# schematicEagle.net
KiCad netlist of a schematic drawn in EAGLE
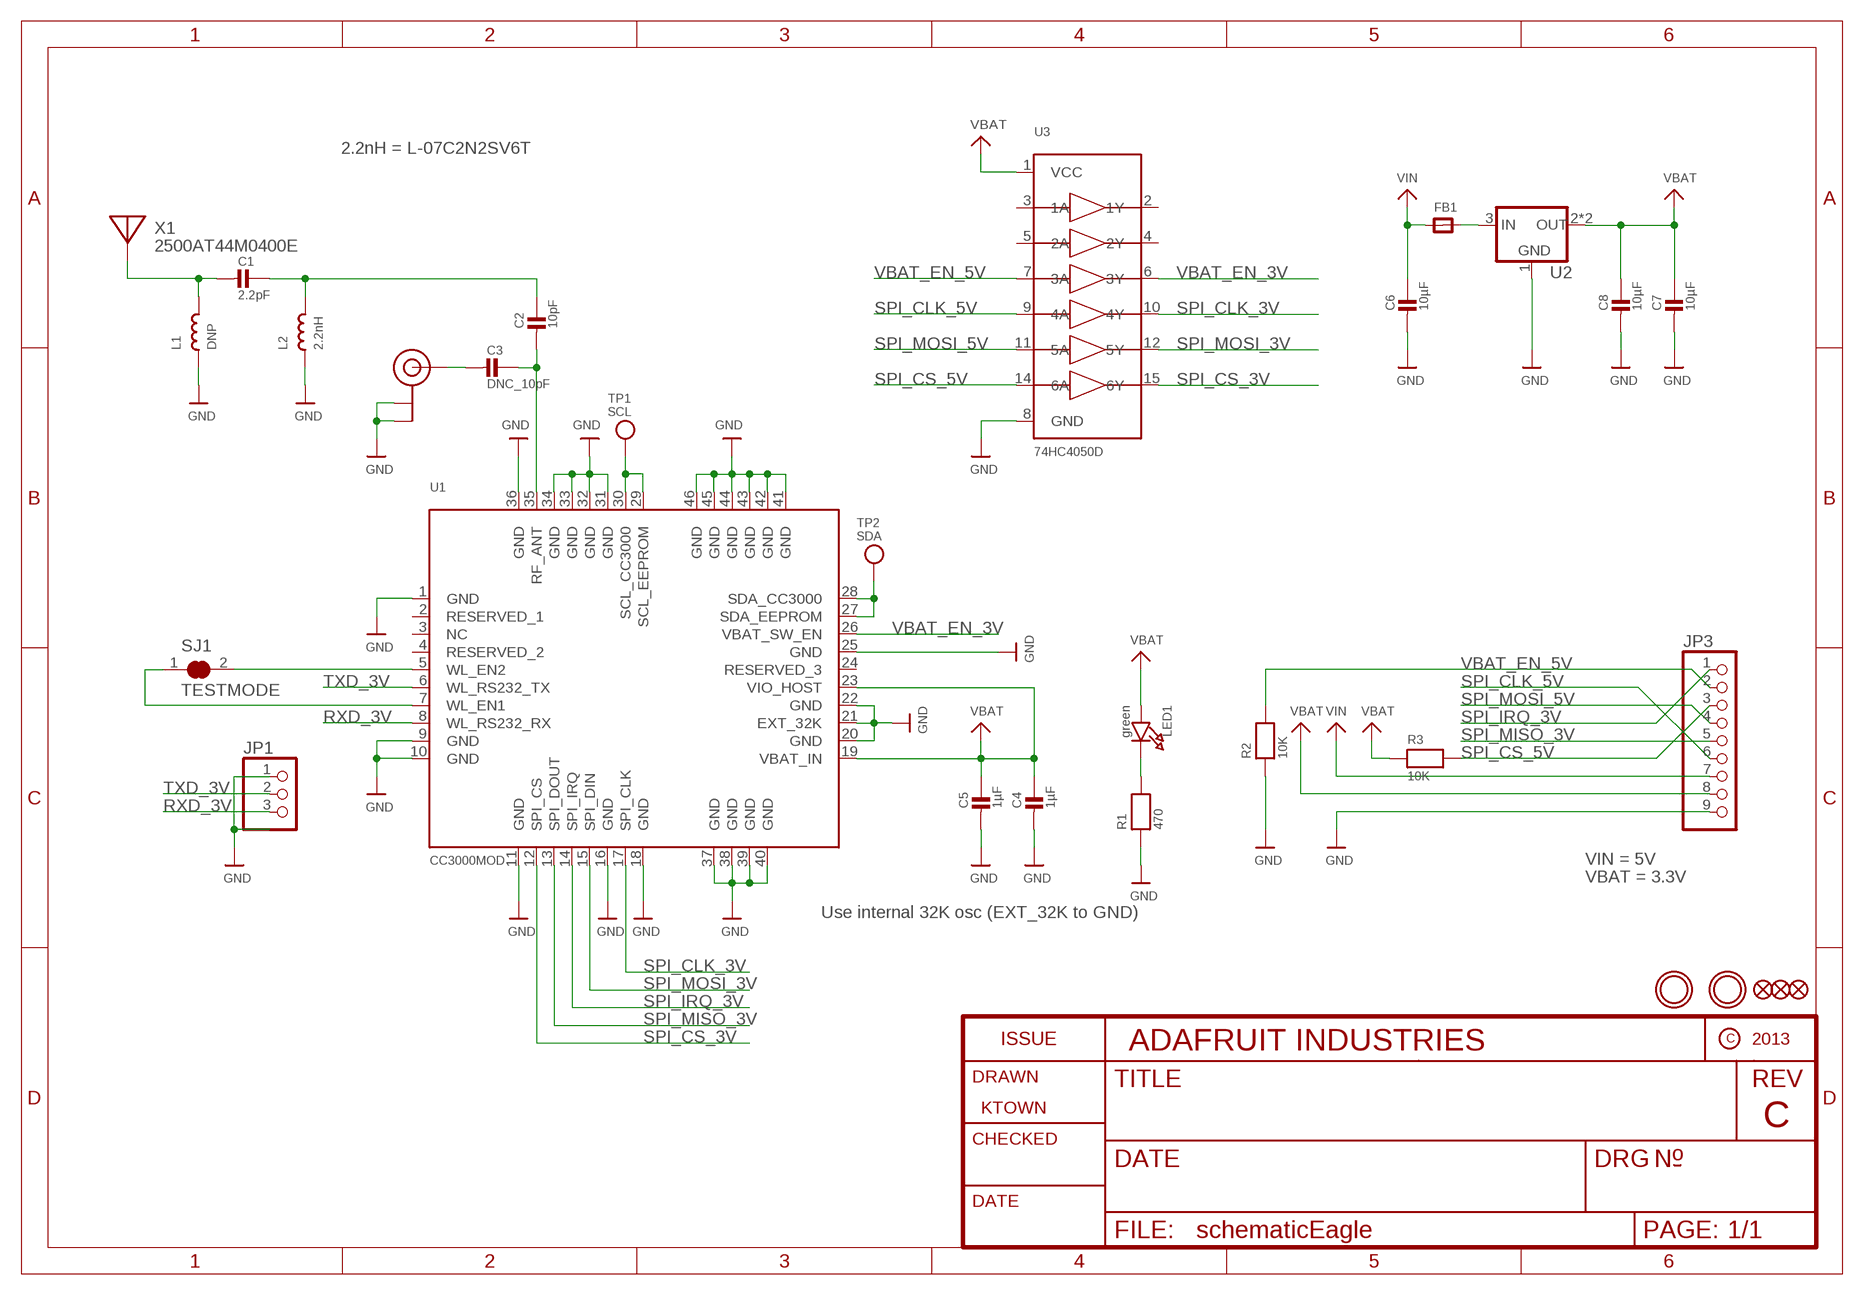
[diagram p0: schematic, sheet 1]

(export (version "E")
  (design (tool "Eeschema 10.0.6"))
  (components
    (comp (ref "C1")
      (value "2.2pF")
      (footprint "eagle-import:_0402")
      (libsource (lib "eagle-import") (part "CAP_CERAMIC_0402"))
    )
    (comp (ref "C2")
      (value "10pF")
      (footprint "eagle-import:_0402")
      (libsource (lib "eagle-import") (part "CAP_CERAMIC_0402"))
    )
    (comp (ref "C3")
      (value "DNC_10pF")
      (footprint "eagle-import:_0402")
      (libsource (lib "eagle-import") (part "CAP_CERAMIC_0402"))
    )
    (comp (ref "C4")
      (value "1µF")
      (footprint "eagle-import:_0805MP")
      (libsource (lib "eagle-import") (part "CAP_CERAMIC_0805MP"))
    )
    (comp (ref "C5")
      (value "1µF")
      (footprint "eagle-import:_0805MP")
      (libsource (lib "eagle-import") (part "CAP_CERAMIC_0805MP"))
    )
    (comp (ref "C6")
      (value "10µF")
      (footprint "eagle-import:_0805MP")
      (libsource (lib "eagle-import") (part "CAP_CERAMIC_0805MP"))
    )
    (comp (ref "C7")
      (value "10µF")
      (footprint "eagle-import:_0805MP")
      (libsource (lib "eagle-import") (part "CAP_CERAMIC_0805MP"))
    )
    (comp (ref "C8")
      (value "10µF")
      (footprint "eagle-import:_0805MP")
      (libsource (lib "eagle-import") (part "CAP_CERAMIC_0805MP"))
    )
    (comp (ref "FB1")
      (value "FERRITE_0805MP")
      (footprint "eagle-import:_0805MP")
      (libsource (lib "eagle-import") (part "FERRITE_0805MP"))
    )
    (comp (ref "FID1")
      (value "FIDUCIAL\"\"")
      (footprint "eagle-import:FIDUCIAL_1MM")
      (libsource (lib "eagle-import") (part "FIDUCIAL{dblquote}{dblquote}"))
    )
    (comp (ref "FID2")
      (value "FIDUCIAL\"\"")
      (footprint "eagle-import:FIDUCIAL_1MM")
      (libsource (lib "eagle-import") (part "FIDUCIAL{dblquote}{dblquote}"))
    )
    (comp (ref "FID3")
      (value "FIDUCIAL\"\"")
      (footprint "eagle-import:FIDUCIAL_1MM")
      (fields (field (name "BOM") "EXCLUDE"))
      (libsource (lib "eagle-import") (part "FIDUCIAL{dblquote}{dblquote}"))
    )
    (comp (ref "JP1")
      (value "HEADER-1X3ROUND")
      (footprint "eagle-import:1X03_ROUND")
      (libsource (lib "eagle-import") (part "HEADER-1X3ROUND"))
    )
    (comp (ref "JP3")
      (value "HEADER-1X970MIL")
      (footprint "eagle-import:1X09_ROUND_70")
      (libsource (lib "eagle-import") (part "HEADER-1X970MIL"))
    )
    (comp (ref "L1")
      (value "DNP")
      (footprint "eagle-import:_0402")
      (libsource (lib "eagle-import") (part "INDUCTOR_0402"))
    )
    (comp (ref "L2")
      (value "2.2nH")
      (footprint "eagle-import:_0402")
      (libsource (lib "eagle-import") (part "INDUCTOR_0402"))
    )
    (comp (ref "LED1")
      (value "green")
      (footprint "eagle-import:CHIPLED_0805_NOOUTLINE")
      (libsource (lib "eagle-import") (part "LED0805_NOOUTLINE"))
    )
    (comp (ref "R1")
      (value "470")
      (footprint "eagle-import:0805-NO")
      (libsource (lib "eagle-import") (part "RESISTOR0805_NOOUTLINE"))
    )
    (comp (ref "R2")
      (value "10K")
      (footprint "eagle-import:_0805MP")
      (libsource (lib "eagle-import") (part "RESISTOR_0805MP"))
    )
    (comp (ref "R3")
      (value "10K")
      (footprint "eagle-import:_0805MP")
      (libsource (lib "eagle-import") (part "RESISTOR_0805MP"))
    )
    (comp (ref "SJ1")
      (value "TESTMODE")
      (footprint "eagle-import:SOLDERJUMPER_CLOSEDWIRE")
      (libsource (lib "eagle-import") (part "SOLDERJUMPER_CLOSED"))
    )
    (comp (ref "TP1")
      (value "SCL")
      (footprint "eagle-import:TESTPOINT_PAD_1MM")
      (libsource (lib "eagle-import") (part "TESTPOINTPAD1MM"))
    )
    (comp (ref "TP2")
      (value "SDA")
      (footprint "eagle-import:TESTPOINT_PAD_1MM")
      (libsource (lib "eagle-import") (part "TESTPOINTPAD1MM"))
    )
    (comp (ref "U$24")
      (value "MOUNTINGHOLE2.5")
      (footprint "eagle-import:MOUNTINGHOLE_2.5_PLATED")
      (libsource (lib "eagle-import") (part "MOUNTINGHOLE2.5"))
    )
    (comp (ref "U$34")
      (value "MOUNTINGHOLE2.5")
      (footprint "eagle-import:MOUNTINGHOLE_2.5_PLATED")
      (libsource (lib "eagle-import") (part "MOUNTINGHOLE2.5"))
    )
    (comp (ref "U$35")
      (value "U.FL")
      (footprint "eagle-import:U.FL")
      (libsource (lib "eagle-import") (part "U.FL"))
    )
    (comp (ref "U1")
      (value "CC3000MOD")
      (footprint "eagle-import:CC3000MOD")
      (libsource (lib "eagle-import") (part "CC3000MOD"))
    )
    (comp (ref "U2")
      (value "VREG_SOT223")
      (footprint "eagle-import:SOT223-R")
      (libsource (lib "eagle-import") (part "VREG_SOT223"))
    )
    (comp (ref "U3")
      (value "74HC4050D")
      (footprint "eagle-import:SOIC16")
      (libsource (lib "eagle-import") (part "74HC4050D"))
    )
    (comp (ref "X1")
      (value "2500AT44M0400E")
      (footprint "eagle-import:ANT_2500AT44M0400")
      (libsource (lib "eagle-import") (part "ANTENNA_JOHANSON_2500AT44M0400"))
    )
  )
  (nets
    (net (code "1") (name "/RXD_3V") (class "Default")
      (node (ref "JP1") (pin "3") (pinfunction "3_3") (pintype "passive"))
      (node (ref "U1") (pin "8") (pinfunction "WL_RS232_RX_8") (pintype "input"))
    )
    (net (code "2") (name "/SPI_CLK_3V") (class "Default")
      (node (ref "U1") (pin "17") (pinfunction "SPI_CLK_17") (pintype "input"))
      (node (ref "U3") (pin "10") (pinfunction "4Y_10") (pintype "bidirectional"))
    )
    (net (code "3") (name "/SPI_CLK_5V") (class "Default")
      (node (ref "JP3") (pin "6") (pinfunction "6_6") (pintype "passive"))
      (node (ref "U3") (pin "9") (pinfunction "4A_9") (pintype "bidirectional"))
    )
    (net (code "4") (name "/SPI_CS_3V") (class "Default")
      (node (ref "U1") (pin "12") (pinfunction "SPI_CS_12") (pintype "input"))
      (node (ref "U3") (pin "15") (pinfunction "6Y_15") (pintype "bidirectional"))
    )
    (net (code "5") (name "/SPI_CS_5V") (class "Default")
      (node (ref "JP3") (pin "3") (pinfunction "3_3") (pintype "passive"))
      (node (ref "R3") (pin "2") (pinfunction "2_2") (pintype "passive"))
      (node (ref "U3") (pin "14") (pinfunction "6A_14") (pintype "bidirectional"))
    )
    (net (code "6") (name "/SPI_IRQ_3V") (class "Default")
      (node (ref "JP3") (pin "1") (pinfunction "1_1") (pintype "passive"))
      (node (ref "U1") (pin "14") (pinfunction "SPI_IRQ_14") (pintype "output"))
    )
    (net (code "7") (name "/SPI_MISO_3V") (class "Default")
      (node (ref "JP3") (pin "5") (pinfunction "5_5") (pintype "passive"))
      (node (ref "U1") (pin "13") (pinfunction "SPI_DOUT_13") (pintype "output"))
    )
    (net (code "8") (name "/SPI_MOSI_3V") (class "Default")
      (node (ref "U1") (pin "15") (pinfunction "SPI_DIN_15") (pintype "input"))
      (node (ref "U3") (pin "12") (pinfunction "5Y_12") (pintype "bidirectional"))
    )
    (net (code "9") (name "/SPI_MOSI_5V") (class "Default")
      (node (ref "JP3") (pin "4") (pinfunction "4_4") (pintype "passive"))
      (node (ref "U3") (pin "11") (pinfunction "5A_11") (pintype "bidirectional"))
    )
    (net (code "10") (name "/TXD_3V") (class "Default")
      (node (ref "JP1") (pin "2") (pinfunction "2_2") (pintype "passive"))
      (node (ref "U1") (pin "6") (pinfunction "WL_RS232_TX_6") (pintype "output"))
    )
    (net (code "11") (name "/VBAT_EN_3V") (class "Default")
      (node (ref "U1") (pin "26") (pinfunction "VBAT_SW_EN_26") (pintype "input"))
      (node (ref "U3") (pin "6") (pinfunction "3Y_6") (pintype "bidirectional"))
    )
    (net (code "12") (name "/VBAT_EN_5V") (class "Default")
      (node (ref "JP3") (pin "2") (pinfunction "2_2") (pintype "passive"))
      (node (ref "R2") (pin "2") (pinfunction "2_2") (pintype "passive"))
      (node (ref "U3") (pin "7") (pinfunction "3A_7") (pintype "bidirectional"))
    )
    (net (code "13") (name "GND") (class "Default")
      (node (ref "C4") (pin "2") (pinfunction "2_2") (pintype "passive"))
      (node (ref "C5") (pin "2") (pinfunction "2_2") (pintype "passive"))
      (node (ref "C6") (pin "2") (pinfunction "2_2") (pintype "passive"))
      (node (ref "C7") (pin "2") (pinfunction "2_2") (pintype "passive"))
      (node (ref "C8") (pin "2") (pinfunction "2_2") (pintype "passive"))
      (node (ref "JP1") (pin "1") (pinfunction "1_1") (pintype "passive"))
      (node (ref "JP3") (pin "9") (pinfunction "9_9") (pintype "passive"))
      (node (ref "L1") (pin "1") (pinfunction "1_1") (pintype "passive"))
      (node (ref "L2") (pin "1") (pinfunction "1_1") (pintype "passive"))
      (node (ref "R1") (pin "1") (pinfunction "1_1") (pintype "passive"))
      (node (ref "R2") (pin "1") (pinfunction "1_1") (pintype "passive"))
      (node (ref "U$35") (pin "P$1") (pinfunction "GND_P$1") (pintype "bidirectional"))
      (node (ref "U$35") (pin "P$2") (pinfunction "GND_P$2") (pintype "bidirectional"))
      (node (ref "U1") (pin "1") (pinfunction "GND_1") (pintype "power_in"))
      (node (ref "U1") (pin "10") (pinfunction "GND_10") (pintype "power_in"))
      (node (ref "U1") (pin "11") (pinfunction "GND_11") (pintype "power_in"))
      (node (ref "U1") (pin "16") (pinfunction "GND_16") (pintype "power_in"))
      (node (ref "U1") (pin "18") (pinfunction "GND_18") (pintype "power_in"))
      (node (ref "U1") (pin "20") (pinfunction "GND_20") (pintype "power_in"))
      (node (ref "U1") (pin "21") (pinfunction "EXT_32K_21") (pintype "bidirectional"))
      (node (ref "U1") (pin "22") (pinfunction "GND_22") (pintype "power_in"))
      (node (ref "U1") (pin "25") (pinfunction "GND_25") (pintype "power_in"))
      (node (ref "U1") (pin "31") (pinfunction "GND_31") (pintype "power_in"))
      (node (ref "U1") (pin "32") (pinfunction "GND_32") (pintype "power_in"))
      (node (ref "U1") (pin "33") (pinfunction "GND_33") (pintype "power_in"))
      (node (ref "U1") (pin "34") (pinfunction "GND_34") (pintype "power_in"))
      (node (ref "U1") (pin "36") (pinfunction "GND_36") (pintype "power_in"))
      (node (ref "U1") (pin "37") (pinfunction "GND_37") (pintype "power_in"))
      (node (ref "U1") (pin "38") (pinfunction "GND_38") (pintype "power_in"))
      (node (ref "U1") (pin "39") (pinfunction "GND_39") (pintype "power_in"))
      (node (ref "U1") (pin "40") (pinfunction "GND_40") (pintype "power_in"))
      (node (ref "U1") (pin "41") (pinfunction "GND_41") (pintype "power_in"))
      (node (ref "U1") (pin "42") (pinfunction "GND_42") (pintype "power_in"))
      (node (ref "U1") (pin "43") (pinfunction "GND_43") (pintype "power_in"))
      (node (ref "U1") (pin "44") (pinfunction "GND_44") (pintype "power_in"))
      (node (ref "U1") (pin "45") (pinfunction "GND_45") (pintype "power_in"))
      (node (ref "U1") (pin "46") (pinfunction "GND_46") (pintype "power_in"))
      (node (ref "U1") (pin "9") (pinfunction "GND_9") (pintype "power_in"))
      (node (ref "U2") (pin "1") (pinfunction "GND_1") (pintype "power_in"))
      (node (ref "U3") (pin "8") (pinfunction "GND_8") (pintype "bidirectional"))
    )
    (net (code "14") (name "Net-(C1-Pad1)") (class "Default")
      (node (ref "C1") (pin "1") (pinfunction "1_1") (pintype "passive"))
      (node (ref "C2") (pin "1") (pinfunction "1_1") (pintype "passive"))
      (node (ref "L2") (pin "2") (pinfunction "2_2") (pintype "passive"))
    )
    (net (code "15") (name "Net-(FB1-P$2)") (class "Default")
      (node (ref "FB1") (pin "2") (pinfunction "P$2_2") (pintype "passive"))
      (node (ref "U2") (pin "3") (pinfunction "IN_3") (pintype "power_in"))
    )
    (net (code "16") (name "Net-(LED1-PadC)") (class "Default")
      (node (ref "LED1") (pin "C") (pinfunction "C_C") (pintype "passive"))
      (node (ref "R1") (pin "2") (pinfunction "2_2") (pintype "passive"))
    )
    (net (code "17") (name "Net-(U$35-SIGNAL)") (class "Default")
      (node (ref "C3") (pin "2") (pinfunction "2_2") (pintype "passive"))
      (node (ref "U$35") (pin "P$3") (pinfunction "SIGNAL_P$3") (pintype "bidirectional"))
    )
    (net (code "18") (name "Net-(U1-RF_ANT)") (class "Default")
      (node (ref "C2") (pin "2") (pinfunction "2_2") (pintype "passive"))
      (node (ref "C3") (pin "1") (pinfunction "1_1") (pintype "passive"))
      (node (ref "U1") (pin "35") (pinfunction "RF_ANT_35") (pintype "bidirectional"))
    )
    (net (code "19") (name "Net-(U1-SCL_CC3000)") (class "Default")
      (node (ref "TP1") (pin "P$1") (pinfunction "P$1_P$1") (pintype "bidirectional"))
      (node (ref "U1") (pin "29") (pinfunction "SCL_EEPROM_29") (pintype "bidirectional"))
      (node (ref "U1") (pin "30") (pinfunction "SCL_CC3000_30") (pintype "bidirectional"))
    )
    (net (code "20") (name "Net-(U1-SDA_CC3000)") (class "Default")
      (node (ref "TP2") (pin "P$1") (pinfunction "P$1_P$1") (pintype "bidirectional"))
      (node (ref "U1") (pin "27") (pinfunction "SDA_EEPROM_27") (pintype "bidirectional"))
      (node (ref "U1") (pin "28") (pinfunction "SDA_CC3000_28") (pintype "bidirectional"))
    )
    (net (code "21") (name "Net-(U1-WL_EN1)") (class "Default")
      (node (ref "SJ1") (pin "1") (pinfunction "1_1") (pintype "passive"))
      (node (ref "U1") (pin "7") (pinfunction "WL_EN1_7") (pintype "input"))
    )
    (net (code "22") (name "Net-(U1-WL_EN2)") (class "Default")
      (node (ref "SJ1") (pin "2") (pinfunction "2_2") (pintype "passive"))
      (node (ref "U1") (pin "5") (pinfunction "WL_EN2_5") (pintype "input"))
    )
    (net (code "23") (name "Net-(X1-P$1)") (class "Default")
      (node (ref "C1") (pin "2") (pinfunction "2_2") (pintype "passive"))
      (node (ref "L1") (pin "2") (pinfunction "2_2") (pintype "passive"))
      (node (ref "X1") (pin "FEED") (pinfunction "P$1_FEED") (pintype "passive"))
    )
    (net (code "24") (name "VBAT") (class "Default")
      (node (ref "C4") (pin "1") (pinfunction "1_1") (pintype "passive"))
      (node (ref "C5") (pin "1") (pinfunction "1_1") (pintype "passive"))
      (node (ref "C7") (pin "1") (pinfunction "1_1") (pintype "passive"))
      (node (ref "C8") (pin "1") (pinfunction "1_1") (pintype "passive"))
      (node (ref "JP3") (pin "8") (pinfunction "8_8") (pintype "passive"))
      (node (ref "LED1") (pin "A") (pinfunction "A_A") (pintype "passive"))
      (node (ref "R3") (pin "1") (pinfunction "1_1") (pintype "passive"))
      (node (ref "U1") (pin "19") (pinfunction "VBAT_IN_19") (pintype "power_in"))
      (node (ref "U1") (pin "23") (pinfunction "VIO_HOST_23") (pintype "power_in"))
      (node (ref "U2") (pin "2") (pinfunction "OUT_2") (pintype "power_in"))
      (node (ref "U2") (pin "4") (pinfunction "OUT_4") (pintype "power_in"))
      (node (ref "U3") (pin "1") (pinfunction "VCC_1") (pintype "bidirectional"))
    )
    (net (code "25") (name "VIN") (class "Default")
      (node (ref "C6") (pin "1") (pinfunction "1_1") (pintype "passive"))
      (node (ref "FB1") (pin "1") (pinfunction "P$1_1") (pintype "passive"))
      (node (ref "JP3") (pin "7") (pinfunction "7_7") (pintype "passive"))
    )
    (net (code "26") (name "unconnected-(U1-NC-Pad3)") (class "Default")
      (node (ref "U1") (pin "3") (pinfunction "NC_3") (pintype "no_connect"))
    )
    (net (code "27") (name "unconnected-(U1-RESERVED_1-Pad2)") (class "Default")
      (node (ref "U1") (pin "2") (pinfunction "RESERVED_1_2") (pintype "bidirectional"))
    )
    (net (code "28") (name "unconnected-(U1-RESERVED_2-Pad4)") (class "Default")
      (node (ref "U1") (pin "4") (pinfunction "RESERVED_2_4") (pintype "bidirectional"))
    )
    (net (code "29") (name "unconnected-(U1-RESERVED_3-Pad24)") (class "Default")
      (node (ref "U1") (pin "24") (pinfunction "RESERVED_3_24") (pintype "bidirectional"))
    )
    (net (code "30") (name "unconnected-(U3-1A-Pad3)") (class "Default")
      (node (ref "U3") (pin "3") (pinfunction "1A_3") (pintype "bidirectional"))
    )
    (net (code "31") (name "unconnected-(U3-1Y-Pad2)") (class "Default")
      (node (ref "U3") (pin "2") (pinfunction "1Y_2") (pintype "bidirectional"))
    )
    (net (code "32") (name "unconnected-(U3-2A-Pad5)") (class "Default")
      (node (ref "U3") (pin "5") (pinfunction "2A_5") (pintype "bidirectional"))
    )
    (net (code "33") (name "unconnected-(U3-2Y-Pad4)") (class "Default")
      (node (ref "U3") (pin "4") (pinfunction "2Y_4") (pintype "bidirectional"))
    )
  )
)
